# karmanDB_power_pyro.net
KiCad netlist of a schematic drawn in Altium Designer
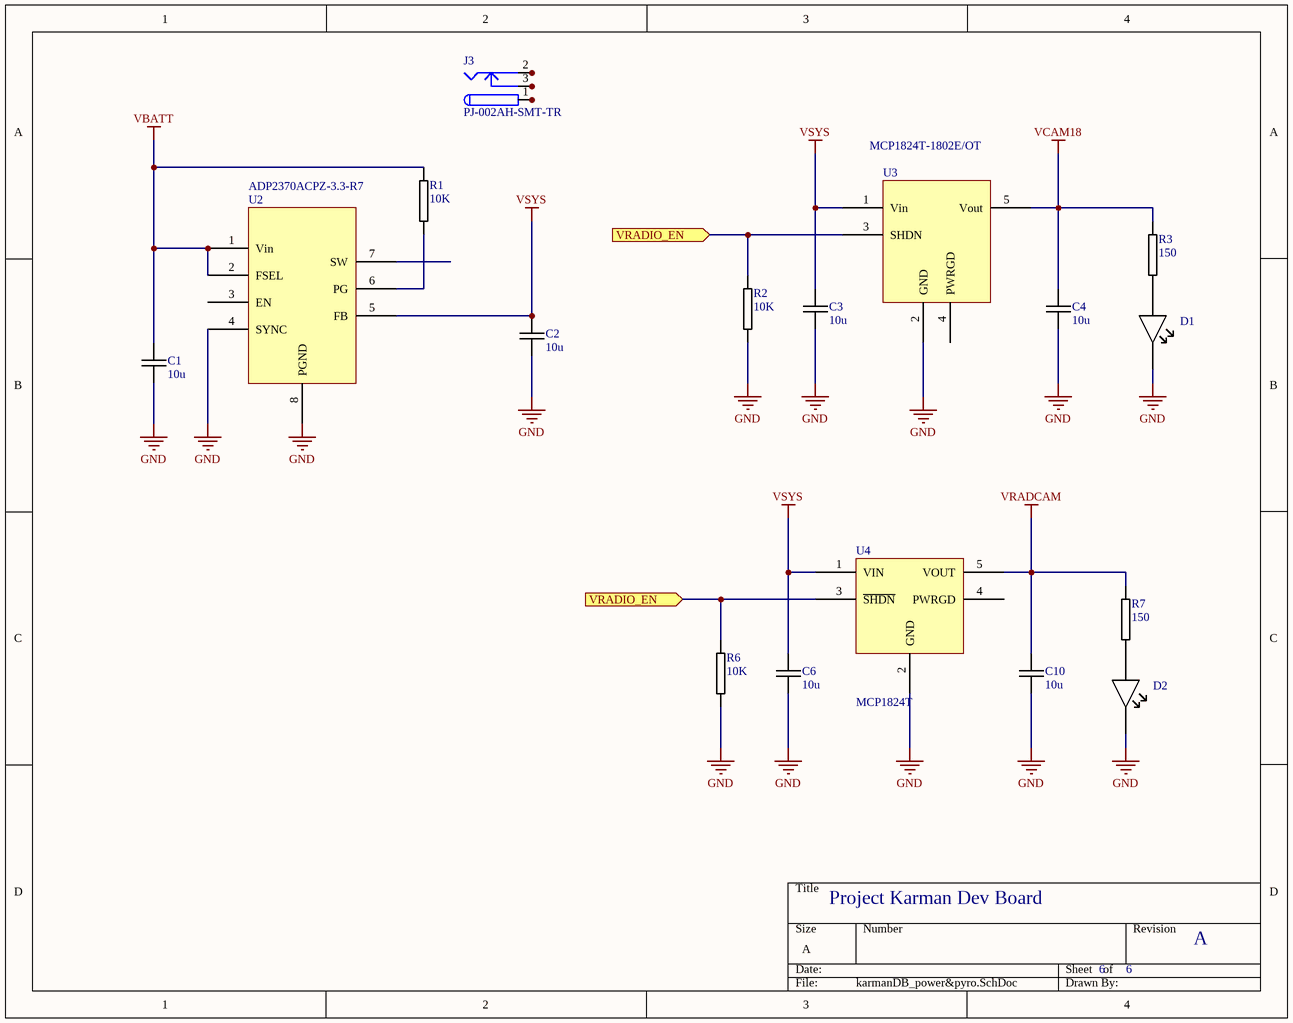
[diagram p0: karmanDB_power&pyro.SchDoc]

(export (version "E")
  (design (tool "Eeschema 10.0.6"))
  (components
    (comp (ref "C1")
      (value "10u")
      (footprint "MURATA_GRM_0603")
      (description "CAP CER 10UF 6.3V 20% X5R 0603")
      (fields
        (field (name "MANUFACTURER") "Murata Electronics North America")
        (field (name "MANUFACTURER PART NUMBER") "GRM188R60J106ME47J")
      )
      (libsource (lib "project_symbols") (part "CAP_MURATA_GRM188R60J106"))
    )
    (comp (ref "C2")
      (value "10u")
      (footprint "MURATA_GRM_0603")
      (description "CAP CER 10UF 6.3V 20% X5R 0603")
      (fields
        (field (name "MANUFACTURER") "Murata Electronics North America")
        (field (name "MANUFACTURER PART NUMBER") "GRM188R60J106ME47J")
      )
      (libsource (lib "project_symbols") (part "CAP_MURATA_GRM188R60J106"))
    )
    (comp (ref "C3")
      (value "10u")
      (footprint "MURATA_GRM_0603")
      (description "CAP CER 10UF 6.3V 20% X5R 0603")
      (fields
        (field (name "MANUFACTURER") "Murata Electronics North America")
        (field (name "MANUFACTURER PART NUMBER") "GRM188R60J106ME47J")
      )
      (libsource (lib "project_symbols") (part "CAP_MURATA_GRM188R60J106"))
    )
    (comp (ref "C4")
      (value "10u")
      (footprint "MURATA_GRM_0603")
      (description "CAP CER 10UF 6.3V 20% X5R 0603")
      (fields
        (field (name "MANUFACTURER") "Murata Electronics North America")
        (field (name "MANUFACTURER PART NUMBER") "GRM188R60J106ME47J")
      )
      (libsource (lib "project_symbols") (part "CAP_MURATA_GRM188R60J106"))
    )
    (comp (ref "C6")
      (value "10u")
      (footprint "MURATA_GRM_0603")
      (description "CAP CER 10UF 6.3V 20% X5R 0603")
      (fields
        (field (name "MANUFACTURER") "Murata Electronics North America")
        (field (name "MANUFACTURER PART NUMBER") "GRM188R60J106ME47J")
      )
      (libsource (lib "project_symbols") (part "CAP_MURATA_GRM188R60J106"))
    )
    (comp (ref "C10")
      (value "10u")
      (footprint "MURATA_GRM_0603")
      (description "CAP CER 10UF 6.3V 20% X5R 0603")
      (fields
        (field (name "MANUFACTURER") "Murata Electronics North America")
        (field (name "MANUFACTURER PART NUMBER") "GRM188R60J106ME47J")
      )
      (libsource (lib "project_symbols") (part "CAP_MURATA_GRM188R60J106"))
    )
    (comp (ref "D1")
      (value "LED_LITEON_LTST-C150CKT")
      (footprint "LITEON_LTST-C150")
      (description "LED RED CLEAR 1206 SMD")
      (fields
        (field (name "MANUFACTURER") "Lite-On Inc")
        (field (name "MANUFACTURER PART NUMBER") "LTST-C150CKT")
      )
      (libsource (lib "project_symbols") (part "LED_LITEON_LTST-C150CKT"))
    )
    (comp (ref "D2")
      (value "LED_LITEON_LTST-C150CKT")
      (footprint "LITEON_LTST-C150")
      (description "LED RED CLEAR 1206 SMD")
      (fields
        (field (name "MANUFACTURER") "Lite-On Inc")
        (field (name "MANUFACTURER PART NUMBER") "LTST-C150CKT")
      )
      (libsource (lib "project_symbols") (part "LED_LITEON_LTST-C150CKT"))
    )
    (comp (ref "J3")
      (value "PJ-002AH-SMT-TR")
      (description "CONN POWER JACK 2.1X5.5MM HI CUR")
      (fields (field (name "MANUFACTURER") "CUI Inc."))
      (libsource (lib "karman_pcb") (part "PJ-002AH-SMT-TR"))
    )
    (comp (ref "R1")
      (value "10K")
      (footprint "MURATA_GRM_0603")
      (description "RES SMD 10K OHM 5% 1/10W 0603")
      (fields
        (field (name "MANUFACTURER") "Panasonic Electronic Components")
        (field (name "MANUFACTURER PART NUMBER") "ERJ-3GEYJ103V")
      )
      (libsource (lib "project_symbols") (part "RES_PANASONIC_ERJ-3GEYJ103V"))
    )
    (comp (ref "R2")
      (value "10K")
      (footprint "MURATA_GRM_0603")
      (description "RES SMD 10K OHM 5% 1/10W 0603")
      (fields
        (field (name "MANUFACTURER") "Panasonic Electronic Components")
        (field (name "MANUFACTURER PART NUMBER") "ERJ-3GEYJ103V")
      )
      (libsource (lib "project_symbols") (part "RES_PANASONIC_ERJ-3GEYJ103V"))
    )
    (comp (ref "R3")
      (value "150")
      (footprint "PANASONIC_ERJ3R")
      (description "RES SMD 150 OHM 5% 1/10W 0603")
      (fields
        (field (name "MANUFACTURER") "Panasonic Electronic Components")
        (field (name "MANUFACTURER PART NUMBER") "ERJ-3GEYJ151V")
      )
      (libsource (lib "project_symbols") (part "RES_PANASONIC_ERJ-3GEYJ151V"))
    )
    (comp (ref "R6")
      (value "10K")
      (footprint "MURATA_GRM_0603")
      (description "RES SMD 10K OHM 5% 1/10W 0603")
      (fields
        (field (name "MANUFACTURER") "Panasonic Electronic Components")
        (field (name "MANUFACTURER PART NUMBER") "ERJ-3GEYJ103V")
      )
      (libsource (lib "project_symbols") (part "RES_PANASONIC_ERJ-3GEYJ103V"))
    )
    (comp (ref "R7")
      (value "150")
      (footprint "PANASONIC_ERJ3R")
      (description "RES SMD 150 OHM 5% 1/10W 0603")
      (fields
        (field (name "MANUFACTURER") "Panasonic Electronic Components")
        (field (name "MANUFACTURER PART NUMBER") "ERJ-3GEYJ151V")
      )
      (libsource (lib "project_symbols") (part "RES_PANASONIC_ERJ-3GEYJ151V"))
    )
    (comp (ref "U2")
      (value "ADP2370ACPZ-3.3-R7")
      (description "IC REG BCK 3.3V 0.8A SYNC 8LFCSP")
      (fields (field (name "MANUFACTURER") "Analog Devices Inc."))
      (libsource (lib "karman_pcb") (part "ADP2370ACPZ-3.3-R7"))
    )
    (comp (ref "U3")
      (value "MCP1824T-1802E/OT")
      (description "IC REG LDO 1.8V 0.3A SOT23-5")
      (fields (field (name "MANUFACTURER") "Microchip Technology"))
      (libsource (lib "karman_pcb") (part "MCP1824T-1802E/OT"))
    )
    (comp (ref "U4")
      (value "MCP1824T")
      (footprint "MICROCHIP_MCP1824/OE")
      (description "IC REG LDO 3V 0.3A SOT23-5")
      (fields
        (field (name "MANUFACTURER") "Microchip Technology")
        (field (name "MANUFACTURER PART NUMBER") "MCP1824T-3002E/OT")
      )
      (libsource (lib "project_symbols") (part "MICROCHIP_MCP1824T-3002E/OT"))
    )
  )
  (nets
    (net (code "1") (name "/VRADIO_EN") (class "Default")
      (node (ref "R2") (pin "1") (pintype "passive"))
      (node (ref "R6") (pin "1") (pintype "passive"))
      (node (ref "U3") (pin "3") (pinfunction "SHDN_3") (pintype "passive"))
      (node (ref "U4") (pin "3") (pinfunction "SHDN_3") (pintype "passive"))
    )
    (net (code "2") (name "GND") (class "Default")
      (node (ref "C1") (pin "2") (pintype "passive"))
      (node (ref "C10") (pin "2") (pintype "passive"))
      (node (ref "C2") (pin "2") (pintype "passive"))
      (node (ref "C3") (pin "2") (pintype "passive"))
      (node (ref "C4") (pin "2") (pintype "passive"))
      (node (ref "C6") (pin "2") (pintype "passive"))
      (node (ref "D1") (pin "K") (pintype "passive"))
      (node (ref "D2") (pin "K") (pintype "passive"))
      (node (ref "R2") (pin "2") (pintype "passive"))
      (node (ref "R6") (pin "2") (pintype "passive"))
      (node (ref "U2") (pin "4") (pinfunction "SYNC_4") (pintype "passive"))
      (node (ref "U2") (pin "8") (pinfunction "PGND_8") (pintype "passive"))
      (node (ref "U3") (pin "2") (pinfunction "GND_2") (pintype "passive"))
      (node (ref "U4") (pin "2") (pinfunction "GND_2") (pintype "passive"))
    )
    (net (code "3") (name "Net-(D1-PadA)") (class "Default")
      (node (ref "D1") (pin "A") (pintype "passive"))
      (node (ref "R3") (pin "2") (pintype "passive"))
    )
    (net (code "4") (name "Net-(D2-PadA)") (class "Default")
      (node (ref "D2") (pin "A") (pintype "passive"))
      (node (ref "R7") (pin "2") (pintype "passive"))
    )
    (net (code "5") (name "Net-(J3-Pad1)") (class "Default")
      (node (ref "J3") (pin "1") (pinfunction "1_1") (pintype "power_in"))
      (node (ref "J3") (pin "1A") (pinfunction "1A_1A") (pintype "power_in"))
      (node (ref "J3") (pin "1B") (pinfunction "1B_1B") (pintype "power_in"))
    )
    (net (code "6") (name "Net-(J3-Pad2)") (class "Default")
      (node (ref "J3") (pin "2") (pinfunction "2_2") (pintype "power_in"))
      (node (ref "J3") (pin "2A") (pinfunction "2A_2A") (pintype "power_in"))
      (node (ref "J3") (pin "2B") (pinfunction "2B_2B") (pintype "power_in"))
    )
    (net (code "7") (name "Net-(J3-Pad3)") (class "Default")
      (node (ref "J3") (pin "3") (pinfunction "3_3") (pintype "power_in"))
      (node (ref "J3") (pin "3A") (pinfunction "3A_3A") (pintype "power_in"))
      (node (ref "J3") (pin "3B") (pinfunction "3B_3B") (pintype "power_in"))
    )
    (net (code "8") (name "Net-(U2-PG)") (class "Default")
      (node (ref "R1") (pin "2") (pintype "passive"))
      (node (ref "U2") (pin "6") (pinfunction "PG_6") (pintype "passive"))
    )
    (net (code "9") (name "VBATT") (class "Default")
      (node (ref "C1") (pin "1") (pintype "passive"))
      (node (ref "R1") (pin "1") (pintype "passive"))
      (node (ref "U2") (pin "1") (pinfunction "Vin_1") (pintype "passive"))
      (node (ref "U2") (pin "2") (pinfunction "FSEL_2") (pintype "passive"))
    )
    (net (code "10") (name "VCAM18") (class "Default")
      (node (ref "C4") (pin "1") (pintype "passive"))
      (node (ref "R3") (pin "1") (pintype "passive"))
      (node (ref "U3") (pin "5") (pinfunction "Vout_5") (pintype "passive"))
    )
    (net (code "11") (name "VRADCAM") (class "Default")
      (node (ref "C10") (pin "1") (pintype "passive"))
      (node (ref "R7") (pin "1") (pintype "passive"))
      (node (ref "U4") (pin "5") (pinfunction "VOUT_5") (pintype "passive"))
    )
    (net (code "12") (name "VSYS") (class "Default")
      (node (ref "C2") (pin "1") (pintype "passive"))
      (node (ref "C3") (pin "1") (pintype "passive"))
      (node (ref "C6") (pin "1") (pintype "passive"))
      (node (ref "U2") (pin "5") (pinfunction "FB_5") (pintype "passive"))
      (node (ref "U3") (pin "1") (pinfunction "Vin_1") (pintype "passive"))
      (node (ref "U4") (pin "1") (pinfunction "VIN_1") (pintype "passive"))
    )
    (net (code "13") (name "unconnected-(U2-EN-Pad3)") (class "Default")
      (node (ref "U2") (pin "3") (pinfunction "EN_3") (pintype "passive"))
    )
    (net (code "14") (name "unconnected-(U2-SW-Pad7)") (class "Default")
      (node (ref "U2") (pin "7") (pinfunction "SW_7") (pintype "passive"))
    )
    (net (code "15") (name "unconnected-(U3-PWRGD-Pad4)") (class "Default")
      (node (ref "U3") (pin "4") (pinfunction "PWRGD_4") (pintype "passive"))
    )
    (net (code "16") (name "unconnected-(U4-PWRGD-Pad4)") (class "Default")
      (node (ref "U4") (pin "4") (pinfunction "PWRGD_4") (pintype "passive"))
    )
  )
)
